# I_DC_Buffering_DIFF.net
KiCad netlist of a schematic drawn in Altium Designer
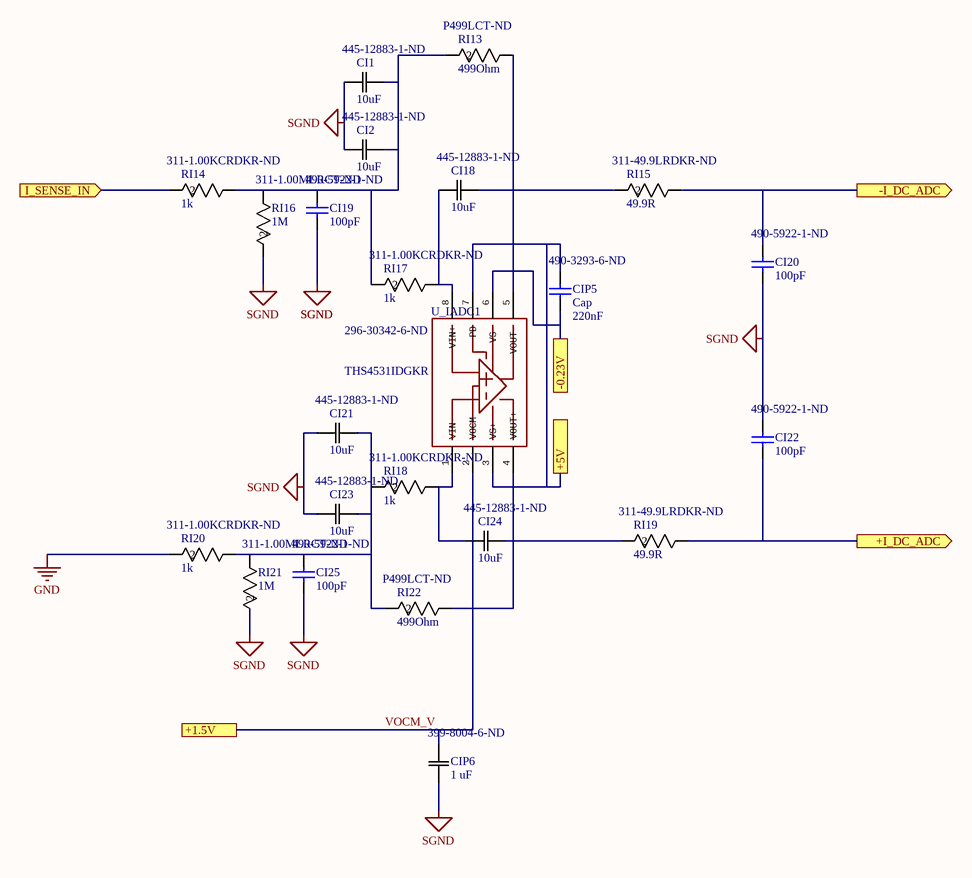
[diagram p0: I_DC_Buffering_DIFF.SchDoc]

(export (version "E")
  (design (tool "Eeschema 10.0.6"))
  (components
    (comp (ref "CI1")
      (value "10uF")
      (footprint "CAP_3216")
      (description "No Description Available")
      (fields
        (field (name "MANUFACTURER_PART_NUMBER") "C3216JB1H106K160AB")
        (field (name "SUPPLIER PART NUMBER 1") "445-12883-1-ND")
        (field (name "MANUFACTURER") "TDK")
        (field (name "COPYRIGHT") "Copyright (C) 2018 Accelerated Designs. All rights reserved")
      )
      (libsource (lib "C3216JB1H106K160AB") (part "C3216JB1H106K160"))
    )
    (comp (ref "CI2")
      (value "10uF")
      (footprint "CAP_3216")
      (description "No Description Available")
      (fields
        (field (name "MANUFACTURER_PART_NUMBER") "C3216JB1H106K160AB")
        (field (name "SUPPLIER PART NUMBER 1") "445-12883-1-ND")
        (field (name "MANUFACTURER") "TDK")
        (field (name "COPYRIGHT") "Copyright (C) 2018 Accelerated Designs. All rights reserved")
      )
      (libsource (lib "C3216JB1H106K160AB") (part "C3216JB1H106K160"))
    )
    (comp (ref "CI18")
      (value "10uF")
      (footprint "CAP_3216")
      (description "No Description Available")
      (fields
        (field (name "MANUFACTURER_PART_NUMBER") "C3216JB1H106K160AB")
        (field (name "SUPPLIER PART NUMBER 1") "445-12883-1-ND")
        (field (name "MANUFACTURER") "TDK")
        (field (name "COPYRIGHT") "Copyright (C) 2018 Accelerated Designs. All rights reserved")
      )
      (libsource (lib "C3216JB1H106K160AB") (part "C3216JB1H106K160"))
    )
    (comp (ref "CI19")
      (value "100pF")
      (footprint "G-155")
      (description "CAP,100PF,+/-5%,C0G,50V,SMD0402")
      (fields
        (field (name "MANUFACTURER") "MURATA")
        (field (name "MANUFACTURER PART NUMBER") "GRM1555C1H101JA01D")
        (field (name "SUPPLIER PART NUMBER 1") "490-5922-1-ND")
      )
      (libsource (lib "Embest") (part "C"))
    )
    (comp (ref "CI20")
      (value "100pF")
      (footprint "G-155")
      (description "CAP,100PF,+/-5%,C0G,50V,SMD0402")
      (fields
        (field (name "MANUFACTURER") "MURATA")
        (field (name "MANUFACTURER PART NUMBER") "GRM1555C1H101JA01D")
        (field (name "SUPPLIER PART NUMBER 1") "490-5922-1-ND")
      )
      (libsource (lib "Embest") (part "C"))
    )
    (comp (ref "CI21")
      (value "10uF")
      (footprint "CAP_3216")
      (description "No Description Available")
      (fields
        (field (name "MANUFACTURER_PART_NUMBER") "C3216JB1H106K160AB")
        (field (name "SUPPLIER PART NUMBER 1") "445-12883-1-ND")
        (field (name "MANUFACTURER") "TDK")
        (field (name "COPYRIGHT") "Copyright (C) 2018 Accelerated Designs. All rights reserved")
      )
      (libsource (lib "C3216JB1H106K160AB") (part "C3216JB1H106K160"))
    )
    (comp (ref "CI22")
      (value "100pF")
      (footprint "G-155")
      (description "CAP,100PF,+/-5%,C0G,50V,SMD0402")
      (fields
        (field (name "MANUFACTURER") "MURATA")
        (field (name "MANUFACTURER PART NUMBER") "GRM1555C1H101JA01D")
        (field (name "SUPPLIER PART NUMBER 1") "490-5922-1-ND")
      )
      (libsource (lib "Embest") (part "C"))
    )
    (comp (ref "CI23")
      (value "10uF")
      (footprint "CAP_3216")
      (description "No Description Available")
      (fields
        (field (name "MANUFACTURER_PART_NUMBER") "C3216JB1H106K160AB")
        (field (name "SUPPLIER PART NUMBER 1") "445-12883-1-ND")
        (field (name "MANUFACTURER") "TDK")
        (field (name "COPYRIGHT") "Copyright (C) 2018 Accelerated Designs. All rights reserved")
      )
      (libsource (lib "C3216JB1H106K160AB") (part "C3216JB1H106K160"))
    )
    (comp (ref "CI24")
      (value "10uF")
      (footprint "CAP_3216")
      (description "No Description Available")
      (fields
        (field (name "MANUFACTURER_PART_NUMBER") "C3216JB1H106K160AB")
        (field (name "SUPPLIER PART NUMBER 1") "445-12883-1-ND")
        (field (name "MANUFACTURER") "TDK")
        (field (name "COPYRIGHT") "Copyright (C) 2018 Accelerated Designs. All rights reserved")
      )
      (libsource (lib "C3216JB1H106K160AB") (part "C3216JB1H106K160"))
    )
    (comp (ref "CI25")
      (value "100pF")
      (footprint "G-155")
      (description "CAP,100PF,+/-5%,C0G,50V,SMD0402")
      (fields
        (field (name "MANUFACTURER") "MURATA")
        (field (name "MANUFACTURER PART NUMBER") "GRM1555C1H101JA01D")
        (field (name "SUPPLIER PART NUMBER 1") "490-5922-1-ND")
      )
      (libsource (lib "Embest") (part "C"))
    )
    (comp (ref "CIP5")
      (value "Cap")
      (footprint "G-188")
      (description "Capacitor")
      (fields
        (field (name "ALTIUM_VALUE") "220nF")
        (field (name "SUPPLIER PART NUMBER 1") "490-3293-6-ND")
        (field (name "MANUFACTURER") "Murata")
        (field (name "MANUFACTURER PART NUMBER") "GRM188R71C224KA01D")
        (field (name "PUBLISHER") "Altium Limited")
      )
      (libsource (lib "Miscellaneous Devices") (part "Cap"))
    )
    (comp (ref "CIP6")
      (value "1 uF")
      (footprint "CAP_C0805")
      (description "No Description Available")
      (fields
        (field (name "MANUFACTURER_PART_NUMBER") "C0805C105K3RACTU")
        (field (name "SUPPLIER PART NUMBER 1") "399-8004-6-ND")
        (field (name "MANUFACTURER") "KEMET")
        (field (name "COPYRIGHT") "Copyright (C) 2018 Accelerated Designs. All rights reserved")
      )
      (libsource (lib "C0805C105K3RACTU") (part "C0805C105K3RACTU"))
    )
    (comp (ref "RI13")
      (value "499Ohm")
      (footprint "RC0402N")
      (description "No Description Available")
      (fields
        (field (name "MANUFACTURER_PART_NUMBER") "ERJ-2RKF4990X")
        (field (name "SUPPLIER PART NUMBER 1") "P499LCT-ND")
        (field (name "MANUFACTURER") "Panasonic")
        (field (name "COPYRIGHT") "Copyright (C) 2018 Accelerated Designs. All rights reserved")
      )
      (libsource (lib "ERJ2RKF4990X") (part "ERJ-2RKF4990X"))
    )
    (comp (ref "RI14")
      (value "1k")
      (footprint "RC0805N")
      (description "No Description Available")
      (fields
        (field (name "MANUFACTURER_PART_NUMBER") "RC0805FR-071KL")
        (field (name "SUPPLIER PART NUMBER 1") "311-1.00KCRDKR-ND")
        (field (name "MANUFACTURER") "Yageo")
        (field (name "COPYRIGHT") "Copyright (C) 2018 Accelerated Designs. All rights reserved")
      )
      (libsource (lib "RC0805FR071KL") (part "RC0805FR-071KL"))
    )
    (comp (ref "RI15")
      (value "49.9R")
      (footprint "RC0402N")
      (description "No Description Available")
      (fields
        (field (name "MANUFACTURER_PART_NUMBER") "RC0402FR-0749R9L")
        (field (name "SUPPLIER PART NUMBER 1") "311-49.9LRDKR-ND")
        (field (name "MANUFACTURER") "Yageo")
        (field (name "COPYRIGHT") "Copyright (C) 2018 Accelerated Designs. All rights reserved")
      )
      (libsource (lib "RC0402FR0749R9L") (part "RC0402FR-0749R9L"))
    )
    (comp (ref "RI16")
      (value "1M")
      (footprint "RC0402N")
      (description "No Description Available")
      (fields
        (field (name "MANUFACTURER_PART_NUMBER") "RC0402FR-071ML")
        (field (name "SUPPLIER PART NUMBER 1") "311-1.00MLRCT-ND")
        (field (name "MANUFACTURER") "Yageo")
        (field (name "COPYRIGHT") "Copyright (C) 2018 Accelerated Designs. All rights reserved")
      )
      (libsource (lib "RC0402FR071ML") (part "RC0402FR-071ML"))
    )
    (comp (ref "RI17")
      (value "1k")
      (footprint "RC0805N")
      (description "No Description Available")
      (fields
        (field (name "MANUFACTURER_PART_NUMBER") "RC0805FR-071KL")
        (field (name "SUPPLIER PART NUMBER 1") "311-1.00KCRDKR-ND")
        (field (name "MANUFACTURER") "Yageo")
        (field (name "COPYRIGHT") "Copyright (C) 2018 Accelerated Designs. All rights reserved")
      )
      (libsource (lib "RC0805FR071KL") (part "RC0805FR-071KL"))
    )
    (comp (ref "RI18")
      (value "1k")
      (footprint "RC0805N")
      (description "No Description Available")
      (fields
        (field (name "MANUFACTURER_PART_NUMBER") "RC0805FR-071KL")
        (field (name "SUPPLIER PART NUMBER 1") "311-1.00KCRDKR-ND")
        (field (name "MANUFACTURER") "Yageo")
        (field (name "COPYRIGHT") "Copyright (C) 2018 Accelerated Designs. All rights reserved")
      )
      (libsource (lib "RC0805FR071KL") (part "RC0805FR-071KL"))
    )
    (comp (ref "RI19")
      (value "49.9R")
      (footprint "RC0402N")
      (description "No Description Available")
      (fields
        (field (name "MANUFACTURER_PART_NUMBER") "RC0402FR-0749R9L")
        (field (name "SUPPLIER PART NUMBER 1") "311-49.9LRDKR-ND")
        (field (name "MANUFACTURER") "Yageo")
        (field (name "COPYRIGHT") "Copyright (C) 2018 Accelerated Designs. All rights reserved")
      )
      (libsource (lib "RC0402FR0749R9L") (part "RC0402FR-0749R9L"))
    )
    (comp (ref "RI20")
      (value "1k")
      (footprint "RC0805N")
      (description "No Description Available")
      (fields
        (field (name "MANUFACTURER_PART_NUMBER") "RC0805FR-071KL")
        (field (name "SUPPLIER PART NUMBER 1") "311-1.00KCRDKR-ND")
        (field (name "MANUFACTURER") "Yageo")
        (field (name "COPYRIGHT") "Copyright (C) 2018 Accelerated Designs. All rights reserved")
      )
      (libsource (lib "RC0805FR071KL") (part "RC0805FR-071KL"))
    )
    (comp (ref "RI21")
      (value "1M")
      (footprint "RC0402N")
      (description "No Description Available")
      (fields
        (field (name "MANUFACTURER_PART_NUMBER") "RC0402FR-071ML")
        (field (name "SUPPLIER PART NUMBER 1") "311-1.00MLRCT-ND")
        (field (name "MANUFACTURER") "Yageo")
        (field (name "COPYRIGHT") "Copyright (C) 2018 Accelerated Designs. All rights reserved")
      )
      (libsource (lib "RC0402FR071ML") (part "RC0402FR-071ML"))
    )
    (comp (ref "RI22")
      (value "499Ohm")
      (footprint "RC0402N")
      (description "No Description Available")
      (fields
        (field (name "MANUFACTURER_PART_NUMBER") "ERJ-2RKF4990X")
        (field (name "SUPPLIER PART NUMBER 1") "P499LCT-ND")
        (field (name "MANUFACTURER") "Panasonic")
        (field (name "COPYRIGHT") "Copyright (C) 2018 Accelerated Designs. All rights reserved")
      )
      (libsource (lib "ERJ2RKF4990X") (part "ERJ-2RKF4990X"))
    )
    (comp (ref "U_IADC1")
      (value "THS4531IDGKR")
      (footprint "DGK8")
      (description "IC OPAMP DIFF 27MHZ RRO 8VSSOP TR")
      (fields (field (name "MANUFACTURER") "TI") (field (name "SUPPLIER PART NUMBER 1") "296-30342-6-ND"))
      (libsource (lib "Embest") (part "THS4531"))
    )
  )
  (nets
    (net (code "1") (name "/+5V") (class "Default")
      (node (ref "CIP5") (pin "2") (pinfunction "2_2") (pintype "passive"))
      (node (ref "U_IADC1") (pin "3") (pinfunction "VS+_3") (pintype "passive"))
      (node (ref "U_IADC1") (pin "7") (pinfunction "PD_7") (pintype "passive"))
    )
    (net (code "2") (name "/+I_DC_ADC") (class "Default")
      (node (ref "CI22") (pin "1") (pinfunction "1_1") (pintype "passive"))
      (node (ref "RI19") (pin "1") (pinfunction "1_1") (pintype "passive"))
    )
    (net (code "3") (name "/-0.23V") (class "Default")
      (node (ref "CIP5") (pin "1") (pinfunction "1_1") (pintype "passive"))
      (node (ref "U_IADC1") (pin "6") (pinfunction "VS-_6") (pintype "passive"))
    )
    (net (code "4") (name "/-I_DC_ADC") (class "Default")
      (node (ref "CI20") (pin "2") (pinfunction "2_2") (pintype "passive"))
      (node (ref "RI15") (pin "1") (pinfunction "1_1") (pintype "passive"))
    )
    (net (code "5") (name "/I_SENSE_IN") (class "Default")
      (node (ref "RI14") (pin "2") (pinfunction "2_2") (pintype "passive"))
    )
    (net (code "6") (name "/VOCM_V") (class "Default")
      (node (ref "CIP6") (pin "2") (pinfunction "2_2") (pintype "passive"))
      (node (ref "U_IADC1") (pin "2") (pinfunction "VOCM_2") (pintype "passive"))
    )
    (net (code "7") (name "GND") (class "Default")
      (node (ref "RI20") (pin "2") (pinfunction "2_2") (pintype "passive"))
    )
    (net (code "8") (name "Net-(CI1-Pad2)") (class "Default")
      (node (ref "CI1") (pin "2") (pinfunction "2_2") (pintype "passive"))
      (node (ref "CI19") (pin "2") (pinfunction "2_2") (pintype "passive"))
      (node (ref "CI2") (pin "2") (pinfunction "2_2") (pintype "passive"))
      (node (ref "RI13") (pin "2") (pinfunction "2_2") (pintype "passive"))
      (node (ref "RI14") (pin "1") (pinfunction "1_1") (pintype "passive"))
      (node (ref "RI16") (pin "1") (pinfunction "1_1") (pintype "passive"))
      (node (ref "RI17") (pin "2") (pinfunction "2_2") (pintype "passive"))
    )
    (net (code "9") (name "Net-(CI21-Pad2)") (class "Default")
      (node (ref "CI21") (pin "2") (pinfunction "2_2") (pintype "passive"))
      (node (ref "CI23") (pin "2") (pinfunction "2_2") (pintype "passive"))
      (node (ref "CI25") (pin "2") (pinfunction "2_2") (pintype "passive"))
      (node (ref "RI18") (pin "2") (pinfunction "2_2") (pintype "passive"))
      (node (ref "RI20") (pin "1") (pinfunction "1_1") (pintype "passive"))
      (node (ref "RI21") (pin "1") (pinfunction "1_1") (pintype "passive"))
      (node (ref "RI22") (pin "2") (pinfunction "2_2") (pintype "passive"))
    )
    (net (code "10") (name "Net-(U_IADC1-VIN+)") (class "Default")
      (node (ref "CI18") (pin "1") (pinfunction "1_1") (pintype "passive"))
      (node (ref "RI17") (pin "1") (pinfunction "1_1") (pintype "passive"))
      (node (ref "U_IADC1") (pin "8") (pinfunction "VIN+_8") (pintype "passive"))
    )
    (net (code "11") (name "Net-(U_IADC1-VIN-)") (class "Default")
      (node (ref "CI24") (pin "1") (pinfunction "1_1") (pintype "passive"))
      (node (ref "RI18") (pin "1") (pinfunction "1_1") (pintype "passive"))
      (node (ref "U_IADC1") (pin "1") (pinfunction "VIN-_1") (pintype "passive"))
    )
    (net (code "12") (name "Net-(U_IADC1-VOUT+)") (class "Default")
      (node (ref "CI24") (pin "2") (pinfunction "2_2") (pintype "passive"))
      (node (ref "RI19") (pin "2") (pinfunction "2_2") (pintype "passive"))
      (node (ref "RI22") (pin "1") (pinfunction "1_1") (pintype "passive"))
      (node (ref "U_IADC1") (pin "4") (pinfunction "VOUT+_4") (pintype "passive"))
    )
    (net (code "13") (name "Net-(U_IADC1-VOUT-)") (class "Default")
      (node (ref "CI18") (pin "2") (pinfunction "2_2") (pintype "passive"))
      (node (ref "RI13") (pin "1") (pinfunction "1_1") (pintype "passive"))
      (node (ref "RI15") (pin "2") (pinfunction "2_2") (pintype "passive"))
      (node (ref "U_IADC1") (pin "5") (pinfunction "VOUT-_5") (pintype "passive"))
    )
    (net (code "14") (name "SGND") (class "Default")
      (node (ref "CI1") (pin "1") (pinfunction "1_1") (pintype "passive"))
      (node (ref "CI19") (pin "1") (pinfunction "1_1") (pintype "passive"))
      (node (ref "CI2") (pin "1") (pinfunction "1_1") (pintype "passive"))
      (node (ref "CI20") (pin "1") (pinfunction "1_1") (pintype "passive"))
      (node (ref "CI21") (pin "1") (pinfunction "1_1") (pintype "passive"))
      (node (ref "CI22") (pin "2") (pinfunction "2_2") (pintype "passive"))
      (node (ref "CI23") (pin "1") (pinfunction "1_1") (pintype "passive"))
      (node (ref "CI25") (pin "1") (pinfunction "1_1") (pintype "passive"))
      (node (ref "CIP6") (pin "1") (pinfunction "1_1") (pintype "passive"))
      (node (ref "RI16") (pin "2") (pinfunction "2_2") (pintype "passive"))
      (node (ref "RI21") (pin "2") (pinfunction "2_2") (pintype "passive"))
    )
  )
)
